# StrobeV4.net
KiCad netlist of a schematic drawn in EAGLE
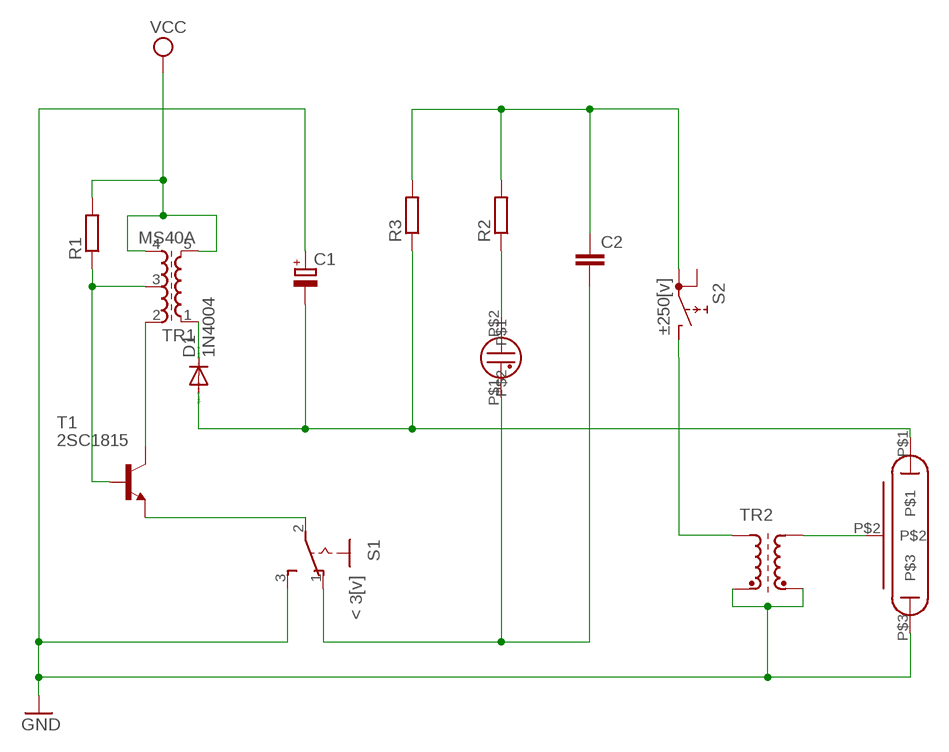
[diagram p0: schematic, sheet 1]

(export (version "E")
  (design (tool "Eeschema 10.0.6"))
  (components
    (comp (ref "C1")
      (value "CPOL-EU140CLH-0810")
      (footprint "eagle-import:140CLH-0810")
      (libsource (lib "eagle-import") (part "CPOL-EU140CLH-0810"))
    )
    (comp (ref "C2")
      (value "C-EU150-054X183")
      (footprint "eagle-import:C150-054X183")
      (libsource (lib "eagle-import") (part "C-EU150-054X183"))
    )
    (comp (ref "D1")
      (value "1N4004")
      (footprint "eagle-import:DO41-10")
      (libsource (lib "eagle-import") (part "1N4004"))
    )
    (comp (ref "R1")
      (value "R-EU_0204/2V")
      (footprint "eagle-import:0204V")
      (libsource (lib "eagle-import") (part "R-EU_0204/2V"))
    )
    (comp (ref "R2")
      (value "R-EU_0204/2V")
      (footprint "eagle-import:0204V")
      (libsource (lib "eagle-import") (part "R-EU_0204/2V"))
    )
    (comp (ref "R3")
      (value "R-EU_0204/2V")
      (footprint "eagle-import:0204V")
      (libsource (lib "eagle-import") (part "R-EU_0204/2V"))
    )
    (comp (ref "S1")
      (value "< 3[v]")
      (footprint "eagle-import:255SB")
      (libsource (lib "eagle-import") (part "255SB"))
    )
    (comp (ref "S2")
      (value "±250[v]")
      (footprint "eagle-import:RDT1034")
      (libsource (lib "eagle-import") (part "RDT1034"))
    )
    (comp (ref "T1")
      (value "2SC1815")
      (footprint "eagle-import:TO92-ECB")
      (libsource (lib "eagle-import") (part "2SC1815"))
    )
    (comp (ref "TR1")
      (value "MS40A")
      (footprint "eagle-import:MS40")
      (libsource (lib "eagle-import") (part "MS40A"))
    )
    (comp (ref "TR2")
      (value "SM-T4")
      (footprint "eagle-import:SM-T4")
      (libsource (lib "eagle-import") (part "SM-T4"))
    )
    (comp (ref "U$1")
      (value "XENON")
      (footprint "eagle-import:XENON")
      (libsource (lib "eagle-import") (part "XENON"))
    )
    (comp (ref "U$2")
      (value "NEON")
      (footprint "eagle-import:NEON")
      (libsource (lib "eagle-import") (part "NEON"))
    )
  )
  (nets
    (net (code "1") (name "GND") (class "Default")
      (node (ref "C1") (pin "+") (pinfunction "+_+") (pintype "passive"))
      (node (ref "S1") (pin "3") (pinfunction "S_3") (pintype "passive"))
      (node (ref "TR2") (pin "2") (pinfunction "E1_2") (pintype "passive"))
      (node (ref "TR2") (pin "4") (pinfunction "E2_4") (pintype "passive"))
      (node (ref "U$1") (pin "P$3") (pinfunction "P$3_P$3") (pintype "bidirectional"))
    )
    (net (code "2") (name "Net-(C1-Pad-)") (class "Default")
      (node (ref "C1") (pin "-") (pinfunction "-_-") (pintype "passive"))
      (node (ref "D1") (pin "A") (pinfunction "A_A") (pintype "passive"))
      (node (ref "R3") (pin "1") (pinfunction "1_1") (pintype "passive"))
      (node (ref "U$1") (pin "P$1") (pinfunction "P$1_P$1") (pintype "bidirectional"))
    )
    (net (code "3") (name "Net-(C2-Pad1)") (class "Default")
      (node (ref "C2") (pin "1") (pinfunction "1_1") (pintype "passive"))
      (node (ref "R2") (pin "2") (pinfunction "2_2") (pintype "passive"))
      (node (ref "R3") (pin "2") (pinfunction "2_2") (pintype "passive"))
      (node (ref "S2") (pin "A1") (pinfunction "A1_A1") (pintype "passive"))
    )
    (net (code "4") (name "Net-(D1-PadC)") (class "Default")
      (node (ref "D1") (pin "C") (pinfunction "C_C") (pintype "passive"))
      (node (ref "TR1") (pin "1") (pinfunction "1_1") (pintype "passive"))
    )
    (net (code "5") (name "Net-(R1-Pad1)") (class "Default")
      (node (ref "R1") (pin "1") (pinfunction "1_1") (pintype "passive"))
      (node (ref "T1") (pin "B") (pinfunction "B_B") (pintype "passive"))
      (node (ref "TR1") (pin "3") (pinfunction "3_3") (pintype "passive"))
    )
    (net (code "6") (name "Net-(R2-Pad1)") (class "Default")
      (node (ref "R2") (pin "1") (pinfunction "1_1") (pintype "passive"))
      (node (ref "U$2") (pin "P$2") (pinfunction "P$2_P$2") (pintype "bidirectional"))
    )
    (net (code "7") (name "Net-(S1-O)") (class "Default")
      (node (ref "C2") (pin "2") (pinfunction "2_2") (pintype "passive"))
      (node (ref "S1") (pin "1") (pinfunction "O_1") (pintype "passive"))
      (node (ref "U$2") (pin "P$1") (pinfunction "P$1_P$1") (pintype "bidirectional"))
    )
    (net (code "8") (name "Net-(S1-P)") (class "Default")
      (node (ref "S1") (pin "2") (pinfunction "P_2") (pintype "passive"))
      (node (ref "T1") (pin "E") (pinfunction "E_E") (pintype "passive"))
    )
    (net (code "9") (name "Net-(T1-PadC)") (class "Default")
      (node (ref "T1") (pin "C") (pinfunction "C_C") (pintype "passive"))
      (node (ref "TR1") (pin "2") (pinfunction "2_2") (pintype "passive"))
    )
    (net (code "10") (name "Net-(TR2-A1)") (class "Default")
      (node (ref "S2") (pin "B") (pinfunction "B_B") (pintype "passive"))
      (node (ref "TR2") (pin "1") (pinfunction "A1_1") (pintype "passive"))
    )
    (net (code "11") (name "Net-(TR2-A2)") (class "Default")
      (node (ref "TR2") (pin "5") (pinfunction "A2_5") (pintype "passive"))
      (node (ref "U$1") (pin "P$2") (pinfunction "P$2_P$2") (pintype "bidirectional"))
    )
    (net (code "12") (name "VCC") (class "Default")
      (node (ref "R1") (pin "2") (pinfunction "2_2") (pintype "passive"))
      (node (ref "TR1") (pin "4") (pinfunction "4_4") (pintype "passive"))
      (node (ref "TR1") (pin "5") (pinfunction "5_5") (pintype "passive"))
    )
    (net (code "13") (name "unconnected-(S2-PadA)") (class "Default")
      (node (ref "S2") (pin "A") (pinfunction "A_A") (pintype "passive"))
    )
  )
)
